# RF_switch_ckt.net
KiCad netlist of a schematic drawn in Altium Designer
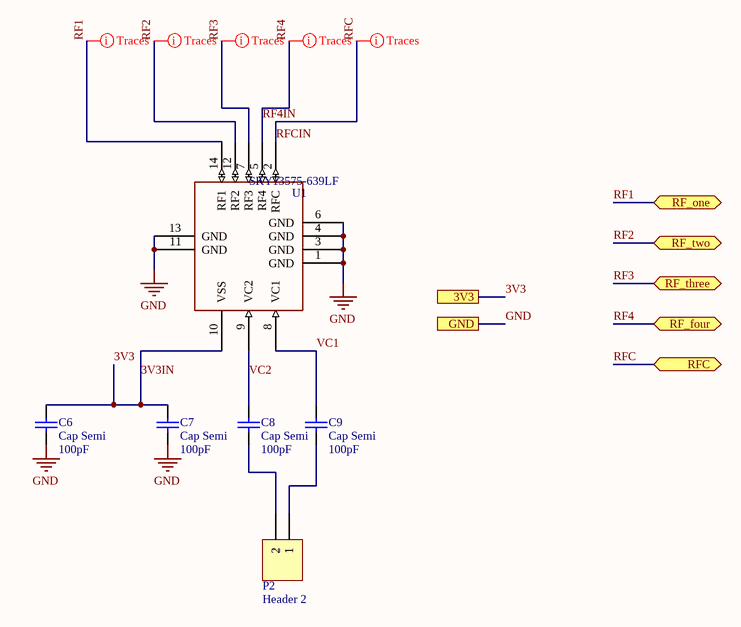
[diagram p0: RF_switch_ckt.SchDoc]

(export (version "E")
  (design (tool "Eeschema 10.0.6"))
  (components
    (comp (ref "C6")
      (value "Cap Semi")
      (footprint "0402")
      (description "Capacitor (Semiconductor SIM Model)")
      (fields (field (name "ALTIUM_VALUE") "100pF") (field (name "PUBLISHER") "Altium Limited"))
      (libsource (lib "Miscellaneous Devices") (part "Cap Semi"))
    )
    (comp (ref "C7")
      (value "Cap Semi")
      (footprint "0402")
      (description "Capacitor (Semiconductor SIM Model)")
      (fields (field (name "ALTIUM_VALUE") "100pF") (field (name "PUBLISHER") "Altium Limited"))
      (libsource (lib "Miscellaneous Devices") (part "Cap Semi"))
    )
    (comp (ref "C8")
      (value "Cap Semi")
      (footprint "0402")
      (description "Capacitor (Semiconductor SIM Model)")
      (fields (field (name "ALTIUM_VALUE") "100pF") (field (name "PUBLISHER") "Altium Limited"))
      (libsource (lib "Miscellaneous Devices") (part "Cap Semi"))
    )
    (comp (ref "C9")
      (value "Cap Semi")
      (footprint "0402")
      (description "Capacitor (Semiconductor SIM Model)")
      (fields (field (name "ALTIUM_VALUE") "100pF") (field (name "PUBLISHER") "Altium Limited"))
      (libsource (lib "Miscellaneous Devices") (part "Cap Semi"))
    )
    (comp (ref "P2")
      (value "Header 2")
      (footprint "HDR1X2")
      (description "Header, 2-Pin")
      (fields (field (name "PUBLISHER") "Altium Limited"))
      (libsource (lib "Miscellaneous Connectors") (part "Header 2"))
    )
    (comp (ref "U1")
      (value "SKY13575-639LF")
      (footprint "*QFN45P200X200X55-15N")
      (libsource (lib "wcsng_altium") (part "SKY13575-639LF"))
    )
  )
  (nets
    (net (code "1") (name "/3V3") (class "Default")
      (node (ref "C6") (pin "2") (pinfunction "2_2") (pintype "passive"))
      (node (ref "C7") (pin "2") (pinfunction "2_2") (pintype "passive"))
      (node (ref "U1") (pin "10") (pinfunction "VSS_10") (pintype "power_in"))
    )
    (net (code "2") (name "/RF1") (class "Default")
      (node (ref "U1") (pin "14") (pinfunction "RF1_14") (pintype "bidirectional"))
    )
    (net (code "3") (name "/RF2") (class "Default")
      (node (ref "U1") (pin "12") (pinfunction "RF2_12") (pintype "bidirectional"))
    )
    (net (code "4") (name "/RF3") (class "Default")
      (node (ref "U1") (pin "7") (pinfunction "RF3_7") (pintype "bidirectional"))
    )
    (net (code "5") (name "/RF4") (class "Default")
      (node (ref "U1") (pin "5") (pinfunction "RF4_5") (pintype "bidirectional"))
    )
    (net (code "6") (name "/RFC") (class "Default")
      (node (ref "U1") (pin "2") (pinfunction "RFC_2") (pintype "bidirectional"))
    )
    (net (code "7") (name "/VC1") (class "Default")
      (node (ref "C9") (pin "2") (pinfunction "2_2") (pintype "passive"))
      (node (ref "U1") (pin "8") (pinfunction "VC1_8") (pintype "input"))
    )
    (net (code "8") (name "/VC2") (class "Default")
      (node (ref "C8") (pin "2") (pinfunction "2_2") (pintype "passive"))
      (node (ref "U1") (pin "9") (pinfunction "VC2_9") (pintype "input"))
    )
    (net (code "9") (name "GND") (class "Default")
      (node (ref "C6") (pin "1") (pinfunction "1_1") (pintype "passive"))
      (node (ref "C7") (pin "1") (pinfunction "1_1") (pintype "passive"))
      (node (ref "U1") (pin "1") (pinfunction "GND_1") (pintype "power_in"))
      (node (ref "U1") (pin "11") (pinfunction "GND_11") (pintype "power_in"))
      (node (ref "U1") (pin "13") (pinfunction "GND_13") (pintype "power_in"))
      (node (ref "U1") (pin "3") (pinfunction "GND_3") (pintype "power_in"))
      (node (ref "U1") (pin "4") (pinfunction "GND_4") (pintype "power_in"))
      (node (ref "U1") (pin "6") (pinfunction "GND_6") (pintype "power_in"))
    )
    (net (code "10") (name "Net-(C8-Pad1)") (class "Default")
      (node (ref "C8") (pin "1") (pinfunction "1_1") (pintype "passive"))
      (node (ref "P2") (pin "2") (pinfunction "2_2") (pintype "passive"))
    )
    (net (code "11") (name "Net-(C9-Pad1)") (class "Default")
      (node (ref "C9") (pin "1") (pinfunction "1_1") (pintype "passive"))
      (node (ref "P2") (pin "1") (pinfunction "1_1") (pintype "passive"))
    )
  )
)
